# pa_blank.net
KiCad netlist of a schematic drawn in Altium Designer
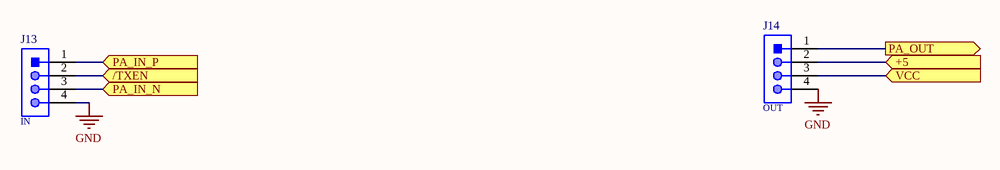
[diagram p0: pa_blank.SchDoc]

(export (version "E")
  (design (tool "Eeschema 10.0.6"))
  (components
    (comp (ref "J13")
      (value "IN")
      (footprint "61300411121")
      (description "THT Vertical Pin Header WR-PHD, Pitch 2.54 mm, Single Row, 4 pins")
      (fields
        (field (name "MANUFACTURER") "Wurth Elektronik")
        (field (name "PART NUMBER") "61300411121")
        (field (name "PUBLISHER") "WurthElektronik")
      )
      (libsource (lib "Altium Content Vault") (part "WE-CN-1P-M-R4"))
    )
    (comp (ref "J14")
      (value "OUT")
      (footprint "61300411121")
      (description "THT Vertical Pin Header WR-PHD, Pitch 2.54 mm, Single Row, 4 pins")
      (fields
        (field (name "MANUFACTURER") "Wurth Elektronik")
        (field (name "PART NUMBER") "61300411121")
        (field (name "PUBLISHER") "WurthElektronik")
      )
      (libsource (lib "Altium Content Vault") (part "WE-CN-1P-M-R4"))
    )
  )
  (nets
    (net (code "1") (name "/+5") (class "Default")
      (node (ref "J14") (pin "2") (pinfunction "2_2") (pintype "passive"))
    )
    (net (code "2") (name "/PA_IN_N") (class "Default")
      (node (ref "J13") (pin "3") (pinfunction "3_3") (pintype "passive"))
    )
    (net (code "3") (name "/PA_IN_P") (class "Default")
      (node (ref "J13") (pin "1") (pinfunction "1_1") (pintype "passive"))
    )
    (net (code "4") (name "/PA_OUT") (class "Default")
      (node (ref "J14") (pin "1") (pinfunction "1_1") (pintype "passive"))
    )
    (net (code "5") (name "/VCC") (class "Default")
      (node (ref "J14") (pin "3") (pinfunction "3_3") (pintype "passive"))
    )
    (net (code "6") (name "/{slash}TXEN") (class "Default")
      (node (ref "J13") (pin "2") (pinfunction "2_2") (pintype "passive"))
    )
    (net (code "7") (name "GND") (class "Default")
      (node (ref "J13") (pin "4") (pinfunction "4_4") (pintype "passive"))
      (node (ref "J14") (pin "4") (pinfunction "4_4") (pintype "passive"))
    )
  )
)
